# SCH_Type_B_2022-05-16.net
KiCad netlist of a schematic drawn in EasyEDA
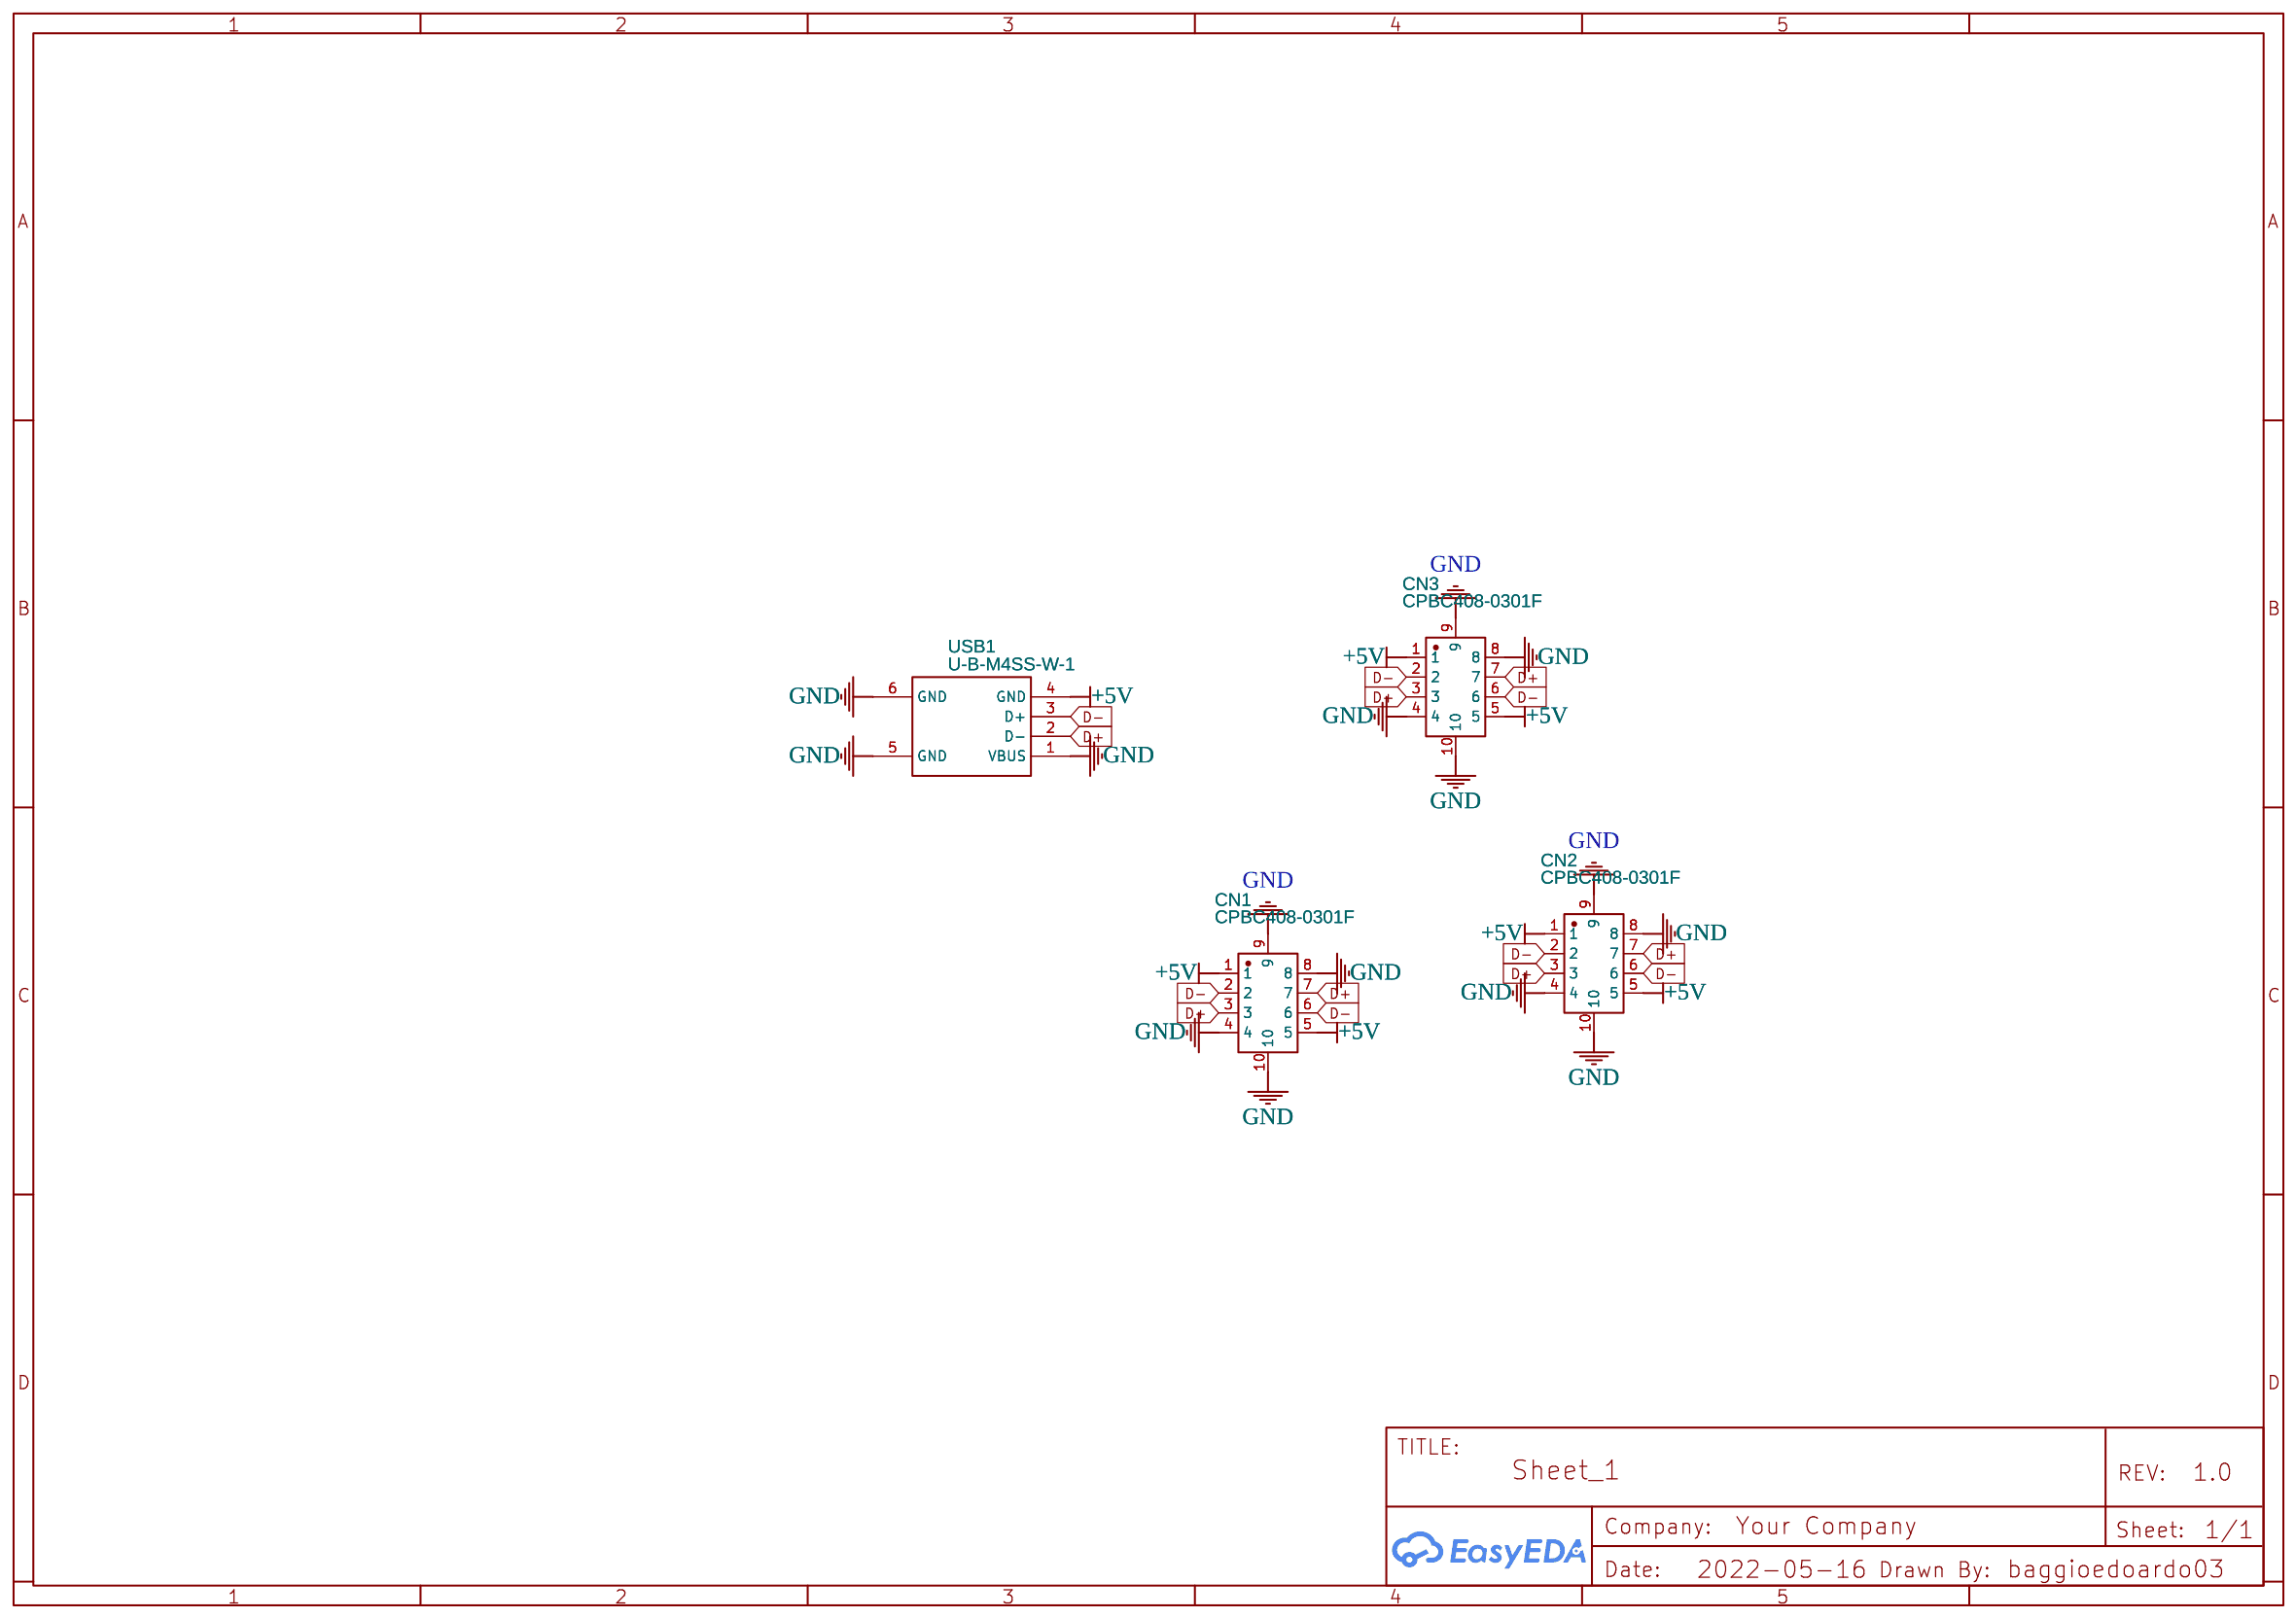
[diagram p0: schematic sheet]

(export (version "E")
  (design (tool "Eeschema 10.0.6"))
  (components
    (comp (ref "CN1")
      (value "CPBC408-0301F")
      (fields (field (name "BOM_Supplier Part") "C841002"))
      (libsource (lib "") (part "CPBC408-0301F"))
    )
    (comp (ref "CN2")
      (value "CPBC408-0301F")
      (fields (field (name "BOM_Supplier Part") "C841002"))
      (libsource (lib "") (part "CPBC408-0301F"))
    )
    (comp (ref "CN3")
      (value "CPBC408-0301F")
      (fields (field (name "BOM_Supplier Part") "C841002"))
      (libsource (lib "") (part "CPBC408-0301F"))
    )
    (comp (ref "USB1")
      (value "U-B-M4SS-W-1")
      (fields (field (name "BOM_Supplier Part") "C530599"))
      (libsource (lib "") (part "U-B-M4SS-W-1"))
    )
  )
  (nets
    (net (code "1") (name "+5V") (class "Default")
      (node (ref "CN1") (pin "1") (pinfunction "1_1") (pintype "unspecified"))
      (node (ref "CN1") (pin "5") (pinfunction "5_5") (pintype "unspecified"))
      (node (ref "CN2") (pin "1") (pinfunction "1_1") (pintype "unspecified"))
      (node (ref "CN2") (pin "5") (pinfunction "5_5") (pintype "unspecified"))
      (node (ref "CN3") (pin "1") (pinfunction "1_1") (pintype "unspecified"))
      (node (ref "CN3") (pin "5") (pinfunction "5_5") (pintype "unspecified"))
      (node (ref "USB1") (pin "4") (pinfunction "GND_4") (pintype "unspecified"))
    )
    (net (code "2") (name "D+") (class "Default")
      (node (ref "CN1") (pin "3") (pinfunction "3_3") (pintype "unspecified"))
      (node (ref "CN1") (pin "7") (pinfunction "7_7") (pintype "unspecified"))
      (node (ref "CN2") (pin "3") (pinfunction "3_3") (pintype "unspecified"))
      (node (ref "CN2") (pin "7") (pinfunction "7_7") (pintype "unspecified"))
      (node (ref "CN3") (pin "3") (pinfunction "3_3") (pintype "unspecified"))
      (node (ref "CN3") (pin "7") (pinfunction "7_7") (pintype "unspecified"))
      (node (ref "USB1") (pin "2") (pinfunction "D-_2") (pintype "unspecified"))
    )
    (net (code "3") (name "D-") (class "Default")
      (node (ref "CN1") (pin "2") (pinfunction "2_2") (pintype "unspecified"))
      (node (ref "CN1") (pin "6") (pinfunction "6_6") (pintype "unspecified"))
      (node (ref "CN2") (pin "2") (pinfunction "2_2") (pintype "unspecified"))
      (node (ref "CN2") (pin "6") (pinfunction "6_6") (pintype "unspecified"))
      (node (ref "CN3") (pin "2") (pinfunction "2_2") (pintype "unspecified"))
      (node (ref "CN3") (pin "6") (pinfunction "6_6") (pintype "unspecified"))
      (node (ref "USB1") (pin "3") (pinfunction "D+_3") (pintype "unspecified"))
    )
    (net (code "4") (name "GND") (class "Default")
      (node (ref "CN1") (pin "10") (pinfunction "10_10") (pintype "unspecified"))
      (node (ref "CN1") (pin "4") (pinfunction "4_4") (pintype "unspecified"))
      (node (ref "CN1") (pin "8") (pinfunction "8_8") (pintype "unspecified"))
      (node (ref "CN1") (pin "9") (pinfunction "9_9") (pintype "unspecified"))
      (node (ref "CN2") (pin "10") (pinfunction "10_10") (pintype "unspecified"))
      (node (ref "CN2") (pin "4") (pinfunction "4_4") (pintype "unspecified"))
      (node (ref "CN2") (pin "8") (pinfunction "8_8") (pintype "unspecified"))
      (node (ref "CN2") (pin "9") (pinfunction "9_9") (pintype "unspecified"))
      (node (ref "CN3") (pin "10") (pinfunction "10_10") (pintype "unspecified"))
      (node (ref "CN3") (pin "4") (pinfunction "4_4") (pintype "unspecified"))
      (node (ref "CN3") (pin "8") (pinfunction "8_8") (pintype "unspecified"))
      (node (ref "CN3") (pin "9") (pinfunction "9_9") (pintype "unspecified"))
      (node (ref "USB1") (pin "1") (pinfunction "VBUS_1") (pintype "unspecified"))
      (node (ref "USB1") (pin "5") (pinfunction "GND_5") (pintype "unspecified"))
      (node (ref "USB1") (pin "6") (pinfunction "GND_6") (pintype "unspecified"))
    )
  )
)
